# decoder.net
KiCad netlist of a schematic drawn in EAGLE
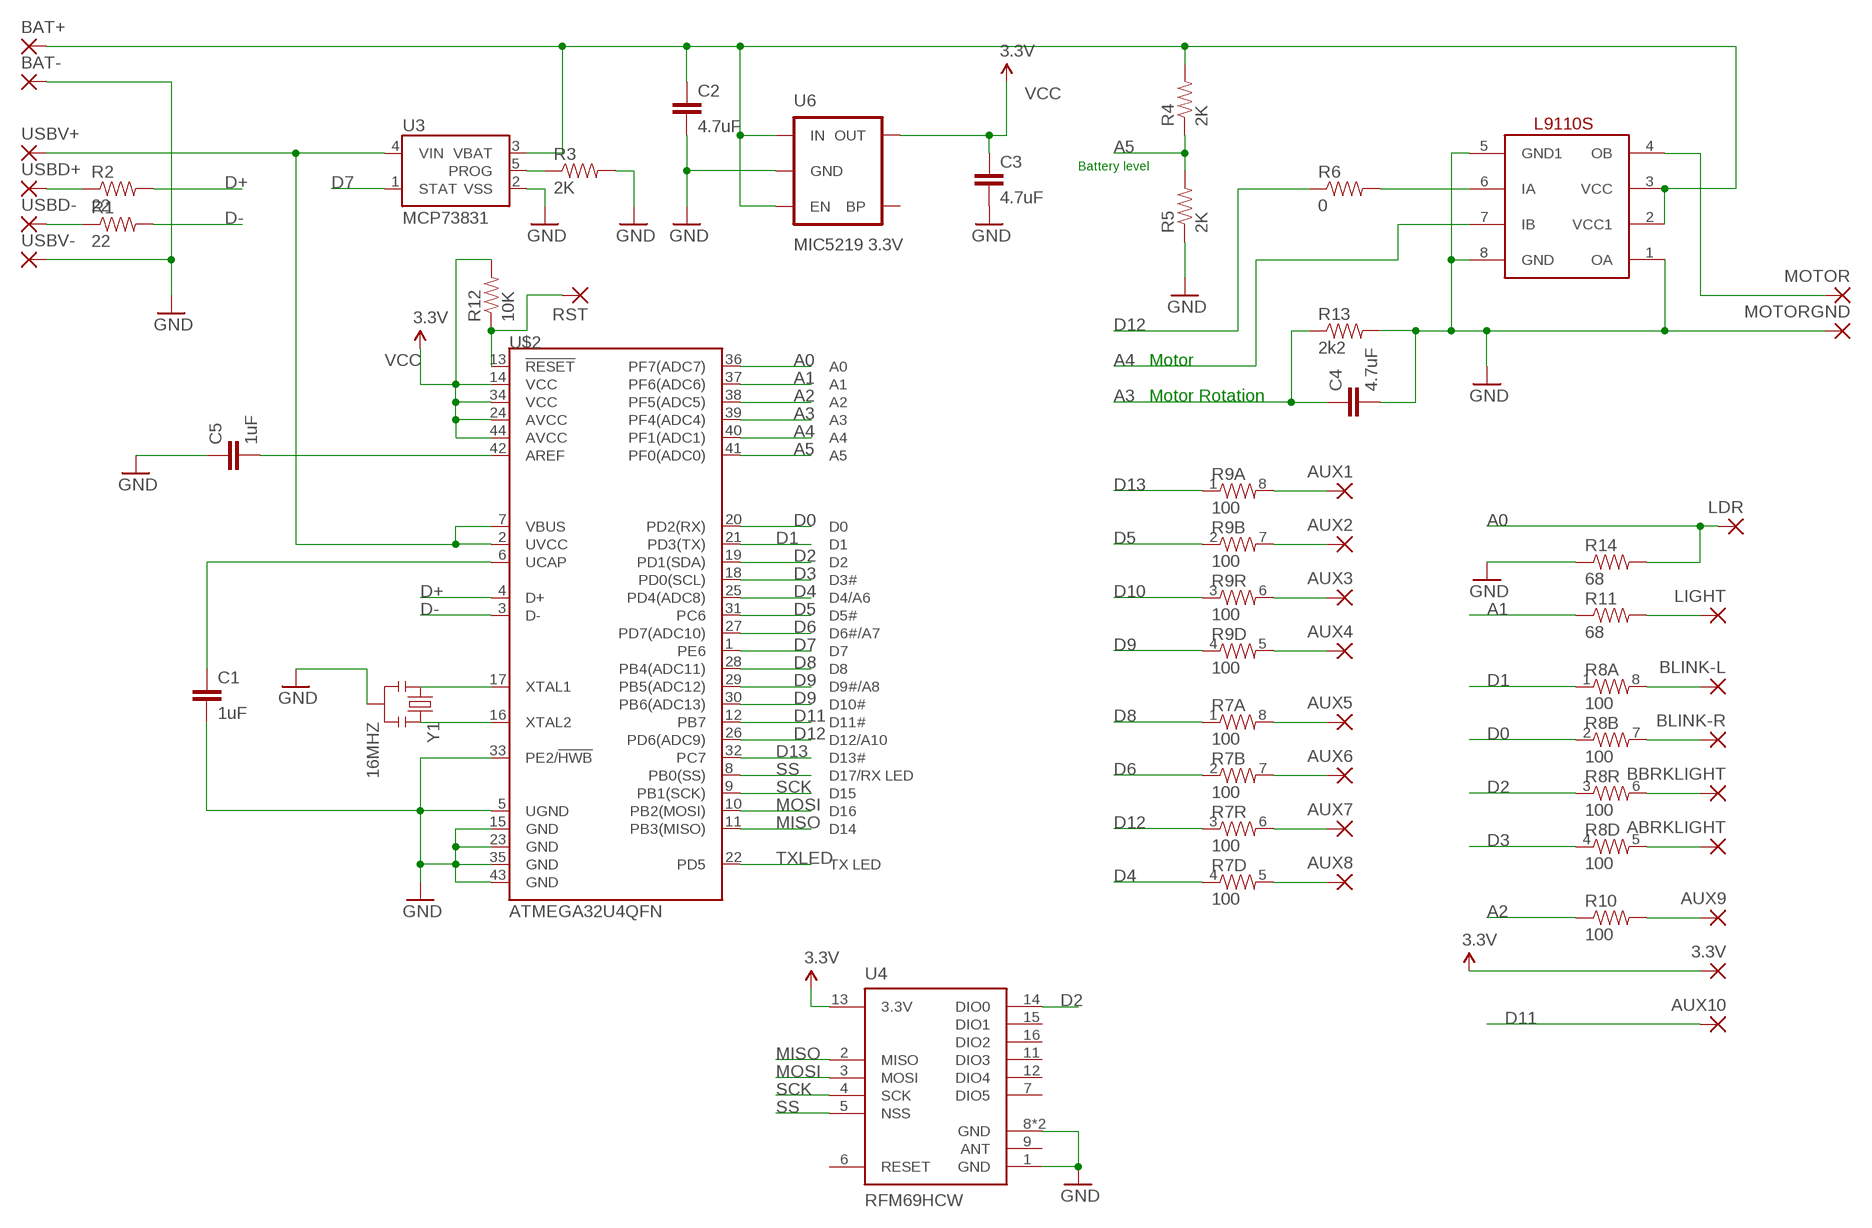
[diagram p0: schematic, sheet 1]

(export (version "E")
  (design (tool "Eeschema 10.0.6"))
  (components
    (comp (ref "3.3V")
      (value "SMD2")
      (footprint "eagle-import:SMD1,27-2,54")
      (libsource (lib "eagle-import") (part "SMD2"))
    )
    (comp (ref "ABRKLIGHT")
      (value "SMD2")
      (footprint "eagle-import:SMD1,27-2,54")
      (libsource (lib "eagle-import") (part "SMD2"))
    )
    (comp (ref "AUX1")
      (value "SMD2")
      (footprint "eagle-import:SMD1,27-2,54")
      (libsource (lib "eagle-import") (part "SMD2"))
    )
    (comp (ref "AUX2")
      (value "SMD2")
      (footprint "eagle-import:SMD1,27-2,54")
      (libsource (lib "eagle-import") (part "SMD2"))
    )
    (comp (ref "AUX3")
      (value "SMD2")
      (footprint "eagle-import:SMD1,27-2,54")
      (libsource (lib "eagle-import") (part "SMD2"))
    )
    (comp (ref "AUX4")
      (value "SMD2")
      (footprint "eagle-import:SMD1,27-2,54")
      (libsource (lib "eagle-import") (part "SMD2"))
    )
    (comp (ref "AUX5")
      (value "SMD2")
      (footprint "eagle-import:SMD1,27-2,54")
      (libsource (lib "eagle-import") (part "SMD2"))
    )
    (comp (ref "AUX6")
      (value "SMD2")
      (footprint "eagle-import:SMD1,27-2,54")
      (libsource (lib "eagle-import") (part "SMD2"))
    )
    (comp (ref "AUX7")
      (value "SMD2")
      (footprint "eagle-import:SMD1,27-2,54")
      (libsource (lib "eagle-import") (part "SMD2"))
    )
    (comp (ref "AUX8")
      (value "SMD2")
      (footprint "eagle-import:SMD1,27-2,54")
      (libsource (lib "eagle-import") (part "SMD2"))
    )
    (comp (ref "AUX9")
      (value "SMD2")
      (footprint "eagle-import:SMD1,27-2,54")
      (libsource (lib "eagle-import") (part "SMD2"))
    )
    (comp (ref "AUX10")
      (value "SMD2")
      (footprint "eagle-import:SMD1,27-2,54")
      (libsource (lib "eagle-import") (part "SMD2"))
    )
    (comp (ref "BAT+")
      (value "SMD2")
      (footprint "eagle-import:SMD1,27-2,54")
      (libsource (lib "eagle-import") (part "SMD2"))
    )
    (comp (ref "BAT-")
      (value "SMD2")
      (footprint "eagle-import:SMD1,27-2,54")
      (libsource (lib "eagle-import") (part "SMD2"))
    )
    (comp (ref "BBRKLIGHT")
      (value "SMD2")
      (footprint "eagle-import:SMD1,27-2,54")
      (libsource (lib "eagle-import") (part "SMD2"))
    )
    (comp (ref "BLINK-L")
      (value "SMD2")
      (footprint "eagle-import:SMD1,27-2,54")
      (libsource (lib "eagle-import") (part "SMD2"))
    )
    (comp (ref "BLINK-R")
      (value "SMD2")
      (footprint "eagle-import:SMD1,27-2,54")
      (libsource (lib "eagle-import") (part "SMD2"))
    )
    (comp (ref "C1")
      (value "1uF")
      (footprint "eagle-import:0805")
      (libsource (lib "eagle-import") (part "CAP0805"))
    )
    (comp (ref "C2")
      (value "4.7uF")
      (footprint "eagle-import:0805")
      (libsource (lib "eagle-import") (part "CAP0805"))
    )
    (comp (ref "C3")
      (value "4.7uF")
      (footprint "eagle-import:0805")
      (libsource (lib "eagle-import") (part "CAP0805"))
    )
    (comp (ref "C4")
      (value "4.7uF")
      (footprint "eagle-import:0805")
      (libsource (lib "eagle-import") (part "CAP0805"))
    )
    (comp (ref "C5")
      (value "1uF")
      (footprint "eagle-import:0805")
      (libsource (lib "eagle-import") (part "CAP0805"))
    )
    (comp (ref "LDR")
      (value "SMD2")
      (footprint "eagle-import:SMD1,27-2,54")
      (libsource (lib "eagle-import") (part "SMD2"))
    )
    (comp (ref "LIGHT")
      (value "SMD2")
      (footprint "eagle-import:SMD1,27-2,54")
      (libsource (lib "eagle-import") (part "SMD2"))
    )
    (comp (ref "MOTOR")
      (value "SMD2")
      (footprint "eagle-import:SMD1,27-2,54")
      (libsource (lib "eagle-import") (part "SMD2"))
    )
    (comp (ref "MOTORGND")
      (value "SMD2")
      (footprint "eagle-import:SMD1,27-2,54")
      (libsource (lib "eagle-import") (part "SMD2"))
    )
    (comp (ref "R1")
      (value "22")
      (footprint "eagle-import:0603-RES")
      (libsource (lib "eagle-import") (part "RESISTOR0603-RES"))
    )
    (comp (ref "R2")
      (value "22")
      (footprint "eagle-import:0603-RES")
      (libsource (lib "eagle-import") (part "RESISTOR0603-RES"))
    )
    (comp (ref "R3")
      (value "2K")
      (footprint "eagle-import:0603-RES")
      (libsource (lib "eagle-import") (part "RESISTOR0603-RES"))
    )
    (comp (ref "R4")
      (value "2K")
      (footprint "eagle-import:0603-RES")
      (libsource (lib "eagle-import") (part "RESISTOR0603-RES"))
    )
    (comp (ref "R5")
      (value "2K")
      (footprint "eagle-import:0603-RES")
      (libsource (lib "eagle-import") (part "RESISTOR0603-RES"))
    )
    (comp (ref "R6")
      (value "0")
      (footprint "eagle-import:0603-RES")
      (libsource (lib "eagle-import") (part "RESISTOR0603-RES"))
    )
    (comp (ref "R7")
      (value "100")
      (footprint "eagle-import:0603-ARV")
      (libsource (lib "eagle-import") (part "RESISTOR-ARRAY0603-ARV"))
    )
    (comp (ref "R8")
      (value "100")
      (footprint "eagle-import:0603-ARV")
      (libsource (lib "eagle-import") (part "RESISTOR-ARRAY0603-ARV"))
    )
    (comp (ref "R9")
      (value "100")
      (footprint "eagle-import:0603-ARV")
      (libsource (lib "eagle-import") (part "RESISTOR-ARRAY0603-ARV"))
    )
    (comp (ref "R10")
      (value "100")
      (footprint "eagle-import:0603-RES")
      (libsource (lib "eagle-import") (part "RESISTOR0603-RES"))
    )
    (comp (ref "R11")
      (value "68")
      (footprint "eagle-import:0603-RES")
      (libsource (lib "eagle-import") (part "RESISTOR0603-RES"))
    )
    (comp (ref "R12")
      (value "10K")
      (footprint "eagle-import:0603-RES")
      (libsource (lib "eagle-import") (part "RESISTOR0603-RES"))
    )
    (comp (ref "R13")
      (value "2k2")
      (footprint "eagle-import:0603-RES")
      (libsource (lib "eagle-import") (part "RESISTOR0603-RES"))
    )
    (comp (ref "R14")
      (value "68")
      (footprint "eagle-import:0603-RES")
      (libsource (lib "eagle-import") (part "RESISTOR0603-RES"))
    )
    (comp (ref "RST")
      (value "SMD2")
      (footprint "eagle-import:SMD1,27-2,54")
      (libsource (lib "eagle-import") (part "SMD2"))
    )
    (comp (ref "U$1")
      (value "L9110S")
      (footprint "eagle-import:SO08")
      (libsource (lib "eagle-import") (part "L9110S"))
    )
    (comp (ref "U$2")
      (value "ATMEGA32U4QFN")
      (footprint "eagle-import:SPARKFUN-DIGITALIC_QFN-44")
      (libsource (lib "eagle-import") (part "ATMEGA32U4QFN"))
    )
    (comp (ref "U3")
      (value "MCP73831")
      (footprint "eagle-import:SOT23-5")
      (libsource (lib "eagle-import") (part "MCP73831"))
    )
    (comp (ref "U4")
      (value "RFM69HCW")
      (footprint "eagle-import:RFM69HCW-XXXS2")
      (libsource (lib "eagle-import") (part "RFM69HCW"))
    )
    (comp (ref "U6")
      (value "MIC5219 3.3V")
      (footprint "eagle-import:SOT23-5")
      (libsource (lib "eagle-import") (part "V_REG_MIC52193.3V"))
    )
    (comp (ref "USBD+")
      (value "SMD2")
      (footprint "eagle-import:SMD1,27-2,54")
      (libsource (lib "eagle-import") (part "SMD2"))
    )
    (comp (ref "USBD-")
      (value "SMD2")
      (footprint "eagle-import:SMD1,27-2,54")
      (libsource (lib "eagle-import") (part "SMD2"))
    )
    (comp (ref "USBV+")
      (value "SMD2")
      (footprint "eagle-import:SMD1,27-2,54")
      (libsource (lib "eagle-import") (part "SMD2"))
    )
    (comp (ref "USBV-")
      (value "SMD2")
      (footprint "eagle-import:SMD1,27-2,54")
      (libsource (lib "eagle-import") (part "SMD2"))
    )
    (comp (ref "Y1")
      (value "16MHZ")
      (footprint "eagle-import:RESONATOR-SMD")
      (libsource (lib "eagle-import") (part "RESONATOR16MHZ"))
    )
  )
  (nets
    (net (code "1") (name "/A0") (class "Default")
      (node (ref "LDR") (pin "1") (pinfunction "P_1") (pintype "passive"))
      (node (ref "R14") (pin "2") (pinfunction "2_2") (pintype "passive"))
      (node (ref "U$2") (pin "36") (pinfunction "PF7(ADC7)_36") (pintype "bidirectional"))
    )
    (net (code "2") (name "/A1") (class "Default")
      (node (ref "R11") (pin "1") (pinfunction "1_1") (pintype "passive"))
      (node (ref "U$2") (pin "37") (pinfunction "PF6(ADC6)_37") (pintype "bidirectional"))
    )
    (net (code "3") (name "/A2") (class "Default")
      (node (ref "R10") (pin "1") (pinfunction "1_1") (pintype "passive"))
      (node (ref "U$2") (pin "38") (pinfunction "PF5(ADC5)_38") (pintype "bidirectional"))
    )
    (net (code "4") (name "/A3") (class "Default")
      (node (ref "C4") (pin "1") (pinfunction "1_1") (pintype "passive"))
      (node (ref "R13") (pin "1") (pinfunction "1_1") (pintype "passive"))
      (node (ref "U$2") (pin "39") (pinfunction "PF4(ADC4)_39") (pintype "bidirectional"))
    )
    (net (code "5") (name "/A4") (class "Default")
      (node (ref "U$1") (pin "7") (pinfunction "IB_7") (pintype "output"))
      (node (ref "U$2") (pin "40") (pinfunction "PF1(ADC1)_40") (pintype "bidirectional"))
    )
    (net (code "6") (name "/A5") (class "Default")
      (node (ref "R4") (pin "1") (pinfunction "1_1") (pintype "passive"))
      (node (ref "R5") (pin "2") (pinfunction "2_2") (pintype "passive"))
      (node (ref "U$2") (pin "41") (pinfunction "PF0(ADC0)_41") (pintype "bidirectional"))
    )
    (net (code "7") (name "/D+") (class "Default")
      (node (ref "R2") (pin "2") (pinfunction "2_2") (pintype "passive"))
      (node (ref "U$2") (pin "4") (pinfunction "D+_4") (pintype "bidirectional"))
    )
    (net (code "8") (name "/D-") (class "Default")
      (node (ref "R1") (pin "2") (pinfunction "2_2") (pintype "passive"))
      (node (ref "U$2") (pin "3") (pinfunction "D-_3") (pintype "bidirectional"))
    )
    (net (code "9") (name "/D0") (class "Default")
      (node (ref "R8") (pin "2") (pinfunction "1_2") (pintype "passive"))
      (node (ref "U$2") (pin "20") (pinfunction "PD2(RX)_20") (pintype "bidirectional"))
    )
    (net (code "10") (name "/D1") (class "Default")
      (node (ref "R8") (pin "1") (pinfunction "1_1") (pintype "passive"))
      (node (ref "U$2") (pin "21") (pinfunction "PD3(TX)_21") (pintype "bidirectional"))
    )
    (net (code "11") (name "/D2") (class "Default")
      (node (ref "R8") (pin "3") (pinfunction "1_3") (pintype "passive"))
      (node (ref "U$2") (pin "19") (pinfunction "PD1(SDA)_19") (pintype "bidirectional"))
      (node (ref "U4") (pin "14") (pinfunction "DIO0_14") (pintype "bidirectional"))
    )
    (net (code "12") (name "/D3") (class "Default")
      (node (ref "R8") (pin "4") (pinfunction "1_4") (pintype "passive"))
      (node (ref "U$2") (pin "18") (pinfunction "PD0(SCL)_18") (pintype "bidirectional"))
    )
    (net (code "13") (name "/D4") (class "Default")
      (node (ref "R7") (pin "4") (pinfunction "1_4") (pintype "passive"))
      (node (ref "U$2") (pin "25") (pinfunction "PD4(ADC8)_25") (pintype "bidirectional"))
    )
    (net (code "14") (name "/D5") (class "Default")
      (node (ref "R9") (pin "2") (pinfunction "1_2") (pintype "passive"))
      (node (ref "U$2") (pin "31") (pinfunction "PC6_31") (pintype "bidirectional"))
    )
    (net (code "15") (name "/D6") (class "Default")
      (node (ref "R7") (pin "2") (pinfunction "1_2") (pintype "passive"))
      (node (ref "U$2") (pin "27") (pinfunction "PD7(ADC10)_27") (pintype "bidirectional"))
    )
    (net (code "16") (name "/D7") (class "Default")
      (node (ref "U$2") (pin "1") (pinfunction "PE6_1") (pintype "bidirectional"))
      (node (ref "U3") (pin "1") (pinfunction "STAT_1") (pintype "output"))
    )
    (net (code "17") (name "/D8") (class "Default")
      (node (ref "R7") (pin "1") (pinfunction "1_1") (pintype "passive"))
      (node (ref "U$2") (pin "28") (pinfunction "PB4(ADC11)_28") (pintype "bidirectional"))
    )
    (net (code "18") (name "/D9") (class "Default")
      (node (ref "R9") (pin "4") (pinfunction "1_4") (pintype "passive"))
      (node (ref "U$2") (pin "29") (pinfunction "PB5(ADC12)_29") (pintype "bidirectional"))
    )
    (net (code "19") (name "/D10") (class "Default")
      (node (ref "R9") (pin "3") (pinfunction "1_3") (pintype "passive"))
      (node (ref "U$2") (pin "30") (pinfunction "PB6(ADC13)_30") (pintype "bidirectional"))
    )
    (net (code "20") (name "/D11") (class "Default")
      (node (ref "AUX10") (pin "1") (pinfunction "P_1") (pintype "passive"))
      (node (ref "U$2") (pin "12") (pinfunction "PB7_12") (pintype "bidirectional"))
    )
    (net (code "21") (name "/D12") (class "Default")
      (node (ref "R6") (pin "1") (pinfunction "1_1") (pintype "passive"))
      (node (ref "R7") (pin "3") (pinfunction "1_3") (pintype "passive"))
      (node (ref "U$2") (pin "26") (pinfunction "PD6(ADC9)_26") (pintype "bidirectional"))
    )
    (net (code "22") (name "/D13") (class "Default")
      (node (ref "R9") (pin "1") (pinfunction "1_1") (pintype "passive"))
      (node (ref "U$2") (pin "32") (pinfunction "PC7_32") (pintype "bidirectional"))
    )
    (net (code "23") (name "/MISO") (class "Default")
      (node (ref "U$2") (pin "11") (pinfunction "PB3(MISO)_11") (pintype "bidirectional"))
      (node (ref "U4") (pin "2") (pinfunction "MISO_2") (pintype "bidirectional"))
    )
    (net (code "24") (name "/MOSI") (class "Default")
      (node (ref "U$2") (pin "10") (pinfunction "PB2(MOSI)_10") (pintype "bidirectional"))
      (node (ref "U4") (pin "3") (pinfunction "MOSI_3") (pintype "input"))
    )
    (net (code "25") (name "/SCK") (class "Default")
      (node (ref "U$2") (pin "9") (pinfunction "PB1(SCK)_9") (pintype "bidirectional"))
      (node (ref "U4") (pin "4") (pinfunction "SCK_4") (pintype "input"))
    )
    (net (code "26") (name "/SS") (class "Default")
      (node (ref "U$2") (pin "8") (pinfunction "PB0(SS)_8") (pintype "bidirectional"))
      (node (ref "U4") (pin "5") (pinfunction "NSS_5") (pintype "input"))
    )
    (net (code "27") (name "/TXLED") (class "Default")
      (node (ref "U$2") (pin "22") (pinfunction "PD5_22") (pintype "bidirectional"))
    )
    (net (code "28") (name "3.3V") (class "Default")
      (node (ref "3.3V") (pin "1") (pinfunction "P_1") (pintype "passive"))
      (node (ref "C3") (pin "1") (pinfunction "1_1") (pintype "passive"))
      (node (ref "R12") (pin "2") (pinfunction "2_2") (pintype "passive"))
      (node (ref "U$2") (pin "14") (pinfunction "VCC_14") (pintype "bidirectional"))
      (node (ref "U$2") (pin "24") (pinfunction "AVCC_24") (pintype "bidirectional"))
      (node (ref "U$2") (pin "34") (pinfunction "VCC_34") (pintype "bidirectional"))
      (node (ref "U$2") (pin "44") (pinfunction "AVCC_44") (pintype "bidirectional"))
      (node (ref "U4") (pin "13") (pinfunction "3.3V_13") (pintype "power_in"))
      (node (ref "U6") (pin "5") (pinfunction "OUT_5") (pintype "passive"))
    )
    (net (code "29") (name "GND") (class "Default")
      (node (ref "BAT-") (pin "1") (pinfunction "P_1") (pintype "passive"))
      (node (ref "C1") (pin "2") (pinfunction "2_2") (pintype "passive"))
      (node (ref "C2") (pin "2") (pinfunction "2_2") (pintype "passive"))
      (node (ref "C3") (pin "2") (pinfunction "2_2") (pintype "passive"))
      (node (ref "C4") (pin "2") (pinfunction "2_2") (pintype "passive"))
      (node (ref "C5") (pin "1") (pinfunction "1_1") (pintype "passive"))
      (node (ref "MOTORGND") (pin "1") (pinfunction "P_1") (pintype "passive"))
      (node (ref "R13") (pin "2") (pinfunction "2_2") (pintype "passive"))
      (node (ref "R14") (pin "1") (pinfunction "1_1") (pintype "passive"))
      (node (ref "R3") (pin "2") (pinfunction "2_2") (pintype "passive"))
      (node (ref "R5") (pin "1") (pinfunction "1_1") (pintype "passive"))
      (node (ref "U$1") (pin "1") (pinfunction "OA_1") (pintype "power_in"))
      (node (ref "U$1") (pin "5") (pinfunction "GND1_5") (pintype "passive"))
      (node (ref "U$1") (pin "8") (pinfunction "GND_8") (pintype "output"))
      (node (ref "U$2") (pin "15") (pinfunction "GND_15") (pintype "bidirectional"))
      (node (ref "U$2") (pin "23") (pinfunction "GND_23") (pintype "bidirectional"))
      (node (ref "U$2") (pin "33") (pinfunction "PE2/~{HWB}_33") (pintype "bidirectional"))
      (node (ref "U$2") (pin "35") (pinfunction "GND_35") (pintype "bidirectional"))
      (node (ref "U$2") (pin "43") (pinfunction "GND_43") (pintype "bidirectional"))
      (node (ref "U$2") (pin "5") (pinfunction "UGND_5") (pintype "bidirectional"))
      (node (ref "U3") (pin "2") (pinfunction "VSS_2") (pintype "power_in"))
      (node (ref "U4") (pin "1") (pinfunction "GND_1") (pintype "power_in"))
      (node (ref "U4") (pin "10") (pinfunction "GND_10") (pintype "power_in"))
      (node (ref "U4") (pin "8") (pinfunction "GND_8") (pintype "power_in"))
      (node (ref "U6") (pin "2") (pinfunction "GND_2") (pintype "input"))
      (node (ref "USBV-") (pin "1") (pinfunction "P_1") (pintype "passive"))
      (node (ref "Y1") (pin "2") (pinfunction "2_2") (pintype "passive"))
    )
    (net (code "30") (name "Net-(ABRKLIGHT-P)") (class "Default")
      (node (ref "ABRKLIGHT") (pin "1") (pinfunction "P_1") (pintype "passive"))
      (node (ref "R8") (pin "5") (pinfunction "2_5") (pintype "passive"))
    )
    (net (code "31") (name "Net-(AUX1-P)") (class "Default")
      (node (ref "AUX1") (pin "1") (pinfunction "P_1") (pintype "passive"))
      (node (ref "R9") (pin "8") (pinfunction "2_8") (pintype "passive"))
    )
    (net (code "32") (name "Net-(AUX2-P)") (class "Default")
      (node (ref "AUX2") (pin "1") (pinfunction "P_1") (pintype "passive"))
      (node (ref "R9") (pin "7") (pinfunction "2_7") (pintype "passive"))
    )
    (net (code "33") (name "Net-(AUX3-P)") (class "Default")
      (node (ref "AUX3") (pin "1") (pinfunction "P_1") (pintype "passive"))
      (node (ref "R9") (pin "6") (pinfunction "2_6") (pintype "passive"))
    )
    (net (code "34") (name "Net-(AUX4-P)") (class "Default")
      (node (ref "AUX4") (pin "1") (pinfunction "P_1") (pintype "passive"))
      (node (ref "R9") (pin "5") (pinfunction "2_5") (pintype "passive"))
    )
    (net (code "35") (name "Net-(AUX5-P)") (class "Default")
      (node (ref "AUX5") (pin "1") (pinfunction "P_1") (pintype "passive"))
      (node (ref "R7") (pin "8") (pinfunction "2_8") (pintype "passive"))
    )
    (net (code "36") (name "Net-(AUX6-P)") (class "Default")
      (node (ref "AUX6") (pin "1") (pinfunction "P_1") (pintype "passive"))
      (node (ref "R7") (pin "7") (pinfunction "2_7") (pintype "passive"))
    )
    (net (code "37") (name "Net-(AUX7-P)") (class "Default")
      (node (ref "AUX7") (pin "1") (pinfunction "P_1") (pintype "passive"))
      (node (ref "R7") (pin "6") (pinfunction "2_6") (pintype "passive"))
    )
    (net (code "38") (name "Net-(AUX8-P)") (class "Default")
      (node (ref "AUX8") (pin "1") (pinfunction "P_1") (pintype "passive"))
      (node (ref "R7") (pin "5") (pinfunction "2_5") (pintype "passive"))
    )
    (net (code "39") (name "Net-(AUX9-P)") (class "Default")
      (node (ref "AUX9") (pin "1") (pinfunction "P_1") (pintype "passive"))
      (node (ref "R10") (pin "2") (pinfunction "2_2") (pintype "passive"))
    )
    (net (code "40") (name "Net-(BAT+-P)") (class "Default")
      (node (ref "BAT+") (pin "1") (pinfunction "P_1") (pintype "passive"))
      (node (ref "C2") (pin "1") (pinfunction "1_1") (pintype "passive"))
      (node (ref "R4") (pin "2") (pinfunction "2_2") (pintype "passive"))
      (node (ref "U$1") (pin "2") (pinfunction "VCC1_2") (pintype "input"))
      (node (ref "U$1") (pin "3") (pinfunction "VCC_3") (pintype "input"))
      (node (ref "U3") (pin "3") (pinfunction "VBAT_3") (pintype "power_in"))
      (node (ref "U6") (pin "1") (pinfunction "IN_1") (pintype "input"))
      (node (ref "U6") (pin "3") (pinfunction "EN_3") (pintype "input"))
    )
    (net (code "41") (name "Net-(BBRKLIGHT-P)") (class "Default")
      (node (ref "BBRKLIGHT") (pin "1") (pinfunction "P_1") (pintype "passive"))
      (node (ref "R8") (pin "6") (pinfunction "2_6") (pintype "passive"))
    )
    (net (code "42") (name "Net-(BLINK-L-P)") (class "Default")
      (node (ref "BLINK-L") (pin "1") (pinfunction "P_1") (pintype "passive"))
      (node (ref "R8") (pin "8") (pinfunction "2_8") (pintype "passive"))
    )
    (net (code "43") (name "Net-(BLINK-R-P)") (class "Default")
      (node (ref "BLINK-R") (pin "1") (pinfunction "P_1") (pintype "passive"))
      (node (ref "R8") (pin "7") (pinfunction "2_7") (pintype "passive"))
    )
    (net (code "44") (name "Net-(LIGHT-P)") (class "Default")
      (node (ref "LIGHT") (pin "1") (pinfunction "P_1") (pintype "passive"))
      (node (ref "R11") (pin "2") (pinfunction "2_2") (pintype "passive"))
    )
    (net (code "45") (name "Net-(MOTOR-P)") (class "Default")
      (node (ref "MOTOR") (pin "1") (pinfunction "P_1") (pintype "passive"))
      (node (ref "U$1") (pin "4") (pinfunction "OB_4") (pintype "power_in"))
    )
    (net (code "46") (name "Net-(RST-P)") (class "Default")
      (node (ref "R12") (pin "1") (pinfunction "1_1") (pintype "passive"))
      (node (ref "RST") (pin "1") (pinfunction "P_1") (pintype "passive"))
      (node (ref "U$2") (pin "13") (pinfunction "~{RESET}_13") (pintype "bidirectional"))
    )
    (net (code "47") (name "Net-(U$1-IA)") (class "Default")
      (node (ref "R6") (pin "2") (pinfunction "2_2") (pintype "passive"))
      (node (ref "U$1") (pin "6") (pinfunction "IA_6") (pintype "passive"))
    )
    (net (code "48") (name "Net-(U$2-AREF)") (class "Default")
      (node (ref "C5") (pin "2") (pinfunction "2_2") (pintype "passive"))
      (node (ref "U$2") (pin "42") (pinfunction "AREF_42") (pintype "bidirectional"))
    )
    (net (code "49") (name "Net-(U$2-UCAP)") (class "Default")
      (node (ref "C1") (pin "1") (pinfunction "1_1") (pintype "passive"))
      (node (ref "U$2") (pin "6") (pinfunction "UCAP_6") (pintype "bidirectional"))
    )
    (net (code "50") (name "Net-(U$2-UVCC)") (class "Default")
      (node (ref "U$2") (pin "2") (pinfunction "UVCC_2") (pintype "bidirectional"))
      (node (ref "U$2") (pin "7") (pinfunction "VBUS_7") (pintype "bidirectional"))
      (node (ref "U3") (pin "4") (pinfunction "VIN_4") (pintype "power_in"))
      (node (ref "USBV+") (pin "1") (pinfunction "P_1") (pintype "passive"))
    )
    (net (code "51") (name "Net-(U$2-XTAL1)") (class "Default")
      (node (ref "U$2") (pin "17") (pinfunction "XTAL1_17") (pintype "bidirectional"))
      (node (ref "Y1") (pin "1") (pinfunction "1_1") (pintype "passive"))
    )
    (net (code "52") (name "Net-(U$2-XTAL2)") (class "Default")
      (node (ref "U$2") (pin "16") (pinfunction "XTAL2_16") (pintype "bidirectional"))
      (node (ref "Y1") (pin "3") (pinfunction "3_3") (pintype "passive"))
    )
    (net (code "53") (name "Net-(U3-PROG)") (class "Default")
      (node (ref "R3") (pin "1") (pinfunction "1_1") (pintype "passive"))
      (node (ref "U3") (pin "5") (pinfunction "PROG_5") (pintype "input"))
    )
    (net (code "54") (name "Net-(USBD+-P)") (class "Default")
      (node (ref "R2") (pin "1") (pinfunction "1_1") (pintype "passive"))
      (node (ref "USBD+") (pin "1") (pinfunction "P_1") (pintype "passive"))
    )
    (net (code "55") (name "Net-(USBD--P)") (class "Default")
      (node (ref "R1") (pin "1") (pinfunction "1_1") (pintype "passive"))
      (node (ref "USBD-") (pin "1") (pinfunction "P_1") (pintype "passive"))
    )
    (net (code "56") (name "unconnected-(U4-ANT-Pad9)") (class "Default")
      (node (ref "U4") (pin "9") (pinfunction "ANT_9") (pintype "passive"))
    )
    (net (code "57") (name "unconnected-(U4-DIO1-Pad15)") (class "Default")
      (node (ref "U4") (pin "15") (pinfunction "DIO1_15") (pintype "bidirectional"))
    )
    (net (code "58") (name "unconnected-(U4-DIO2-Pad16)") (class "Default")
      (node (ref "U4") (pin "16") (pinfunction "DIO2_16") (pintype "bidirectional"))
    )
    (net (code "59") (name "unconnected-(U4-DIO3-Pad11)") (class "Default")
      (node (ref "U4") (pin "11") (pinfunction "DIO3_11") (pintype "bidirectional"))
    )
    (net (code "60") (name "unconnected-(U4-DIO4-Pad12)") (class "Default")
      (node (ref "U4") (pin "12") (pinfunction "DIO4_12") (pintype "bidirectional"))
    )
    (net (code "61") (name "unconnected-(U4-DIO5-Pad7)") (class "Default")
      (node (ref "U4") (pin "7") (pinfunction "DIO5_7") (pintype "bidirectional"))
    )
    (net (code "62") (name "unconnected-(U4-RESET-Pad6)") (class "Default")
      (node (ref "U4") (pin "6") (pinfunction "RESET_6") (pintype "input"))
    )
    (net (code "63") (name "unconnected-(U6-BP-Pad4)") (class "Default")
      (node (ref "U6") (pin "4") (pinfunction "BP_4") (pintype "input"))
    )
  )
)
